# thit_draw103.net
KiCad netlist of a schematic drawn in EAGLE
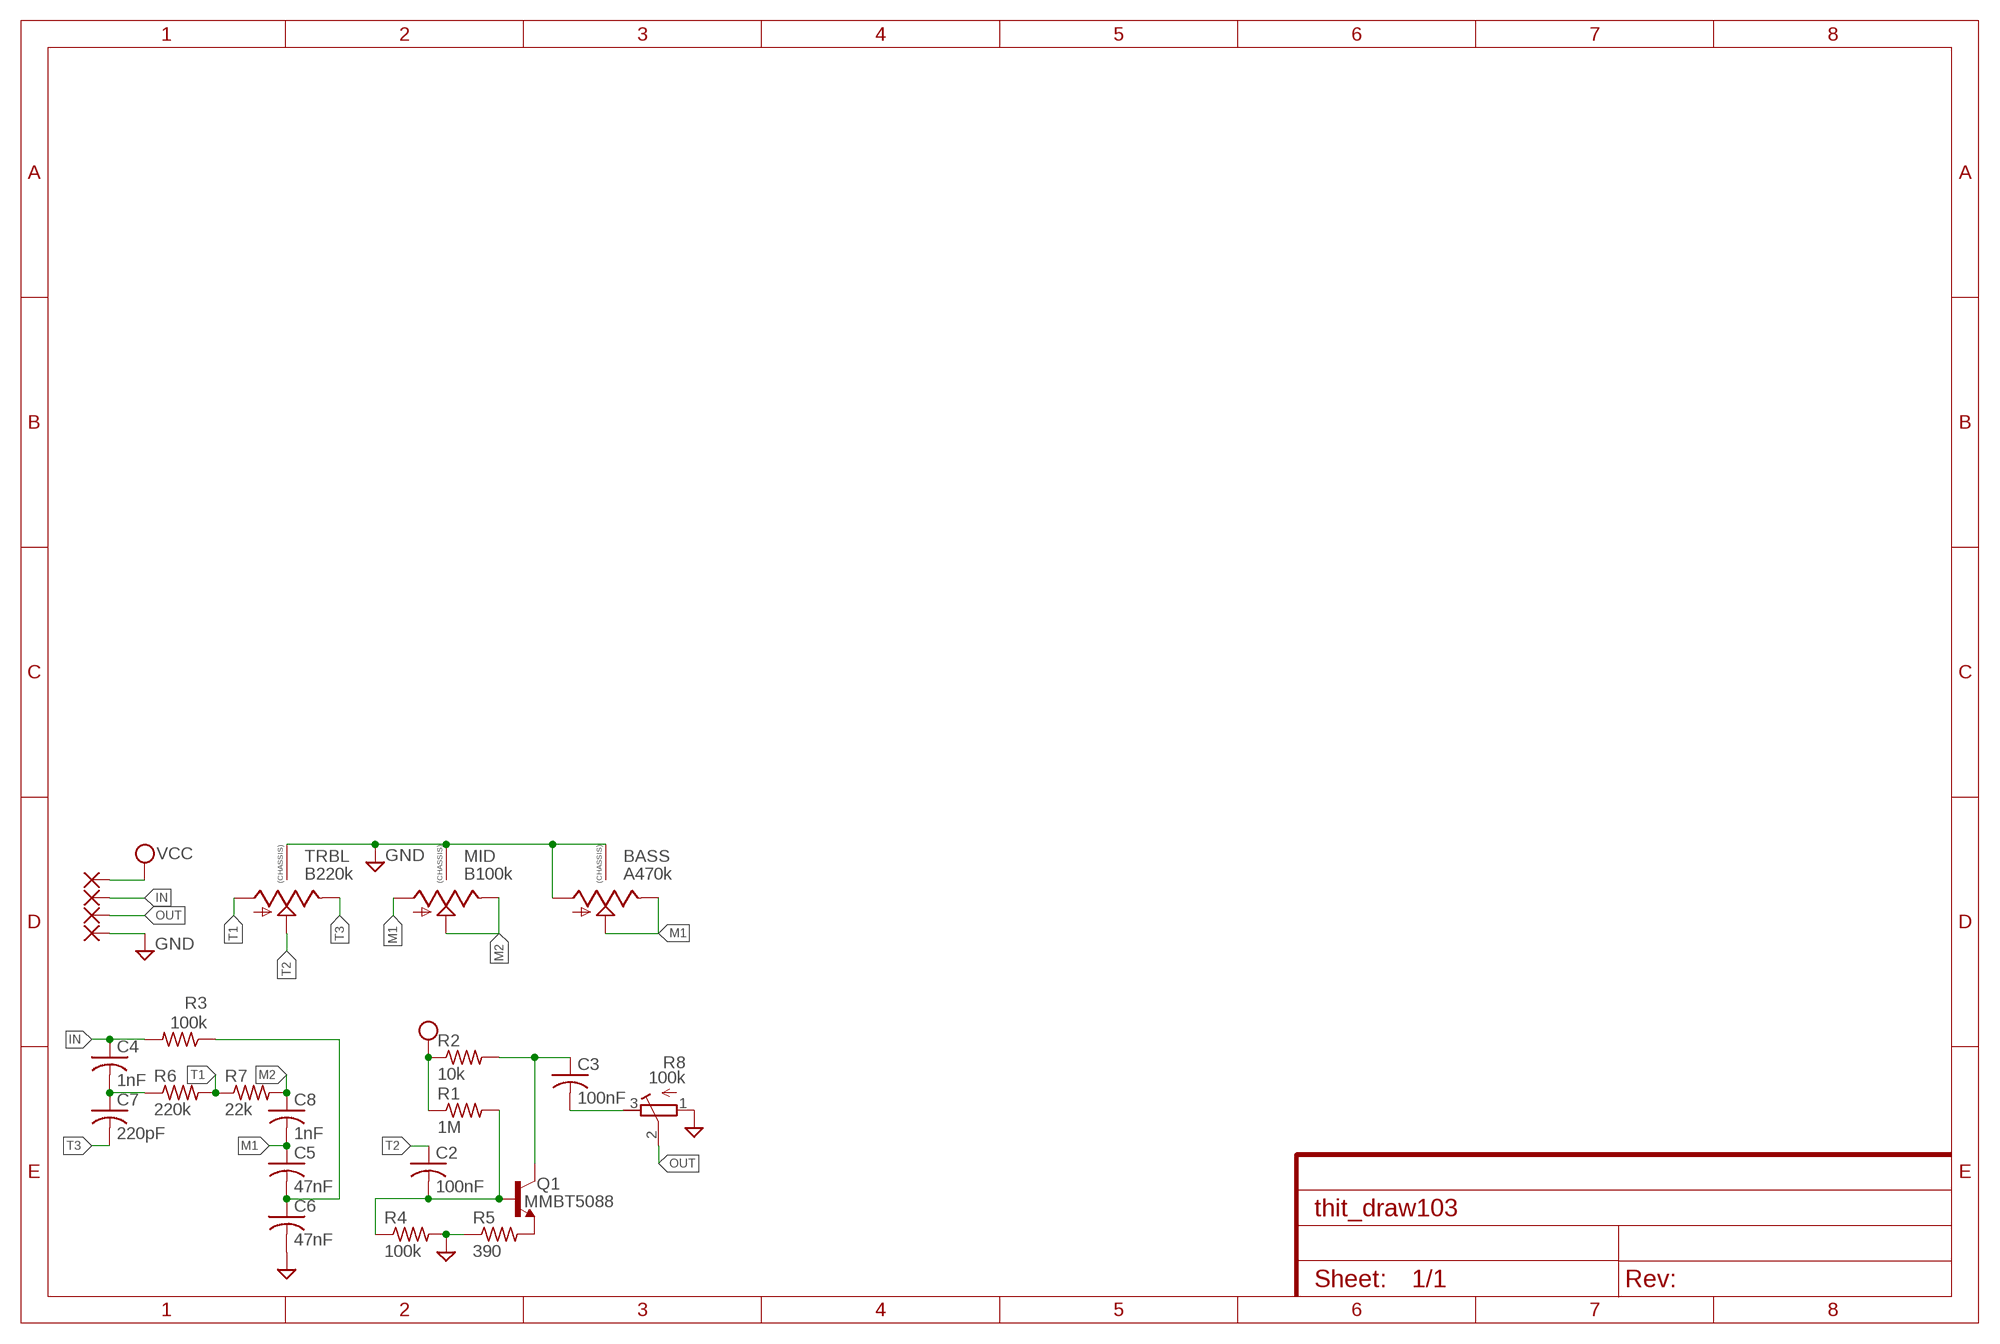
[diagram p0: schematic, sheet 1]

(export (version "E")
  (design (tool "Eeschema 10.0.6"))
  (components
    (comp (ref "BASS")
      (value "A470k")
      (footprint "eagle-import:9MM_SNAP-IN_POT")
      (libsource (lib "eagle-import") (part "9MM_SNAP-IN_POT_CHASSIS"))
    )
    (comp (ref "C2")
      (value "100nF")
      (footprint "eagle-import:C0603")
      (libsource (lib "eagle-import") (part "C-USC0603"))
    )
    (comp (ref "C3")
      (value "100nF")
      (footprint "eagle-import:C0603")
      (libsource (lib "eagle-import") (part "C-USC0603"))
    )
    (comp (ref "C4")
      (value "1nF")
      (footprint "eagle-import:C0603")
      (libsource (lib "eagle-import") (part "C-USC0603"))
    )
    (comp (ref "C5")
      (value "47nF")
      (footprint "eagle-import:C0603")
      (libsource (lib "eagle-import") (part "C-USC0603"))
    )
    (comp (ref "C6")
      (value "47nF")
      (footprint "eagle-import:C0603")
      (libsource (lib "eagle-import") (part "C-USC0603"))
    )
    (comp (ref "C7")
      (value "220pF")
      (footprint "eagle-import:C0603")
      (libsource (lib "eagle-import") (part "C-USC0603"))
    )
    (comp (ref "C8")
      (value "1nF")
      (footprint "eagle-import:C0603")
      (libsource (lib "eagle-import") (part "C-USC0603"))
    )
    (comp (ref "MID")
      (value "B100k")
      (footprint "eagle-import:9MM_SNAP-IN_POT")
      (libsource (lib "eagle-import") (part "9MM_SNAP-IN_POT_CHASSIS"))
    )
    (comp (ref "PAD1")
      (value "1,6/0,8")
      (footprint "eagle-import:1,6_0,8")
      (libsource (lib "eagle-import") (part "1,6/0,8"))
    )
    (comp (ref "PAD2")
      (value "1,6/0,8")
      (footprint "eagle-import:1,6_0,8")
      (libsource (lib "eagle-import") (part "1,6/0,8"))
    )
    (comp (ref "PAD3")
      (value "1,6/0,8")
      (footprint "eagle-import:1,6_0,8")
      (libsource (lib "eagle-import") (part "1,6/0,8"))
    )
    (comp (ref "PAD4")
      (value "1,6/0,8")
      (footprint "eagle-import:1,6_0,8")
      (libsource (lib "eagle-import") (part "1,6/0,8"))
    )
    (comp (ref "Q1")
      (value "MMBT5088")
      (footprint "eagle-import:SOT23-BEC")
      (fields (field (name "MF") "ON Semiconductor"))
      (libsource (lib "eagle-import") (part "MMBT5088"))
    )
    (comp (ref "R1")
      (value "1M")
      (footprint "eagle-import:R0603")
      (libsource (lib "eagle-import") (part "R-US_R0603"))
    )
    (comp (ref "R2")
      (value "10k")
      (footprint "eagle-import:R0603")
      (libsource (lib "eagle-import") (part "R-US_R0603"))
    )
    (comp (ref "R3")
      (value "100k")
      (footprint "eagle-import:R0603")
      (libsource (lib "eagle-import") (part "R-US_R0603"))
    )
    (comp (ref "R4")
      (value "100k")
      (footprint "eagle-import:R0603")
      (libsource (lib "eagle-import") (part "R-US_R0603"))
    )
    (comp (ref "R5")
      (value "390")
      (footprint "eagle-import:R0603")
      (libsource (lib "eagle-import") (part "R-US_R0603"))
    )
    (comp (ref "R6")
      (value "220k")
      (footprint "eagle-import:R0603")
      (libsource (lib "eagle-import") (part "R-US_R0603"))
    )
    (comp (ref "R7")
      (value "22k")
      (footprint "eagle-import:R0603")
      (libsource (lib "eagle-import") (part "R-US_R0603"))
    )
    (comp (ref "R8")
      (value "100k")
      (footprint "eagle-import:RTRIM3224X")
      (libsource (lib "eagle-import") (part "R-TRIMM3224X"))
    )
    (comp (ref "TRBL")
      (value "B220k")
      (footprint "eagle-import:9MM_SNAP-IN_POT")
      (libsource (lib "eagle-import") (part "9MM_SNAP-IN_POT_CHASSIS"))
    )
  )
  (nets
    (net (code "1") (name "GND") (class "Default")
      (node (ref "BASS") (pin "1") (pinfunction "A_1") (pintype "passive"))
      (node (ref "BASS") (pin "CHASSIS1") (pinfunction "P$1_CHASSIS1") (pintype "passive"))
      (node (ref "BASS") (pin "CHASSIS2") (pinfunction "P$1_CHASSIS2") (pintype "passive"))
      (node (ref "C6") (pin "2") (pinfunction "2_2") (pintype "passive"))
      (node (ref "MID") (pin "CHASSIS1") (pinfunction "P$1_CHASSIS1") (pintype "passive"))
      (node (ref "MID") (pin "CHASSIS2") (pinfunction "P$1_CHASSIS2") (pintype "passive"))
      (node (ref "PAD4") (pin "1") (pinfunction "P_1") (pintype "passive"))
      (node (ref "R4") (pin "2") (pinfunction "2_2") (pintype "passive"))
      (node (ref "R5") (pin "1") (pinfunction "1_1") (pintype "passive"))
      (node (ref "R8") (pin "1") (pinfunction "A_1") (pintype "passive"))
      (node (ref "TRBL") (pin "CHASSIS1") (pinfunction "P$1_CHASSIS1") (pintype "passive"))
      (node (ref "TRBL") (pin "CHASSIS2") (pinfunction "P$1_CHASSIS2") (pintype "passive"))
    )
    (net (code "2") (name "IN") (class "Default")
      (node (ref "C4") (pin "1") (pinfunction "1_1") (pintype "passive"))
      (node (ref "PAD2") (pin "1") (pinfunction "P_1") (pintype "passive"))
      (node (ref "R3") (pin "2") (pinfunction "2_2") (pintype "passive"))
    )
    (net (code "3") (name "M1") (class "Default")
      (node (ref "BASS") (pin "2") (pinfunction "S_2") (pintype "passive"))
      (node (ref "BASS") (pin "3") (pinfunction "E_3") (pintype "passive"))
      (node (ref "C5") (pin "1") (pinfunction "1_1") (pintype "passive"))
      (node (ref "C8") (pin "2") (pinfunction "2_2") (pintype "passive"))
      (node (ref "MID") (pin "1") (pinfunction "A_1") (pintype "passive"))
    )
    (net (code "4") (name "M2") (class "Default")
      (node (ref "C8") (pin "1") (pinfunction "1_1") (pintype "passive"))
      (node (ref "MID") (pin "2") (pinfunction "S_2") (pintype "passive"))
      (node (ref "MID") (pin "3") (pinfunction "E_3") (pintype "passive"))
      (node (ref "R7") (pin "2") (pinfunction "2_2") (pintype "passive"))
    )
    (net (code "5") (name "Net-(C2-Pad2)") (class "Default")
      (node (ref "C2") (pin "2") (pinfunction "2_2") (pintype "passive"))
      (node (ref "Q1") (pin "B") (pinfunction "B_B") (pintype "passive"))
      (node (ref "R1") (pin "2") (pinfunction "2_2") (pintype "passive"))
      (node (ref "R4") (pin "1") (pinfunction "1_1") (pintype "passive"))
    )
    (net (code "6") (name "Net-(C3-Pad1)") (class "Default")
      (node (ref "C3") (pin "1") (pinfunction "1_1") (pintype "passive"))
      (node (ref "Q1") (pin "C") (pinfunction "C_C") (pintype "passive"))
      (node (ref "R2") (pin "2") (pinfunction "2_2") (pintype "passive"))
    )
    (net (code "7") (name "Net-(C4-Pad2)") (class "Default")
      (node (ref "C4") (pin "2") (pinfunction "2_2") (pintype "passive"))
      (node (ref "C7") (pin "1") (pinfunction "1_1") (pintype "passive"))
      (node (ref "R6") (pin "1") (pinfunction "1_1") (pintype "passive"))
    )
    (net (code "8") (name "Net-(C5-Pad2)") (class "Default")
      (node (ref "C5") (pin "2") (pinfunction "2_2") (pintype "passive"))
      (node (ref "C6") (pin "1") (pinfunction "1_1") (pintype "passive"))
      (node (ref "R3") (pin "1") (pinfunction "1_1") (pintype "passive"))
    )
    (net (code "9") (name "Net-(Q1-PadE)") (class "Default")
      (node (ref "Q1") (pin "E") (pinfunction "E_E") (pintype "passive"))
      (node (ref "R5") (pin "2") (pinfunction "2_2") (pintype "passive"))
    )
    (net (code "10") (name "Net-(R8-E)") (class "Default")
      (node (ref "C3") (pin "2") (pinfunction "2_2") (pintype "passive"))
      (node (ref "R8") (pin "3") (pinfunction "E_3") (pintype "passive"))
    )
    (net (code "11") (name "OUT") (class "Default")
      (node (ref "PAD3") (pin "1") (pinfunction "P_1") (pintype "passive"))
      (node (ref "R8") (pin "2") (pinfunction "S_2") (pintype "passive"))
    )
    (net (code "12") (name "T1") (class "Default")
      (node (ref "R6") (pin "2") (pinfunction "2_2") (pintype "passive"))
      (node (ref "R7") (pin "1") (pinfunction "1_1") (pintype "passive"))
      (node (ref "TRBL") (pin "1") (pinfunction "A_1") (pintype "passive"))
    )
    (net (code "13") (name "T2") (class "Default")
      (node (ref "C2") (pin "1") (pinfunction "1_1") (pintype "passive"))
      (node (ref "TRBL") (pin "2") (pinfunction "S_2") (pintype "passive"))
    )
    (net (code "14") (name "T3") (class "Default")
      (node (ref "C7") (pin "2") (pinfunction "2_2") (pintype "passive"))
      (node (ref "TRBL") (pin "3") (pinfunction "E_3") (pintype "passive"))
    )
    (net (code "15") (name "VCC") (class "Default")
      (node (ref "PAD1") (pin "1") (pinfunction "P_1") (pintype "passive"))
      (node (ref "R1") (pin "1") (pinfunction "1_1") (pintype "passive"))
      (node (ref "R2") (pin "1") (pinfunction "1_1") (pintype "passive"))
    )
  )
)
